# SCH_AirQuality.net
KiCad netlist of a schematic drawn in EasyEDA
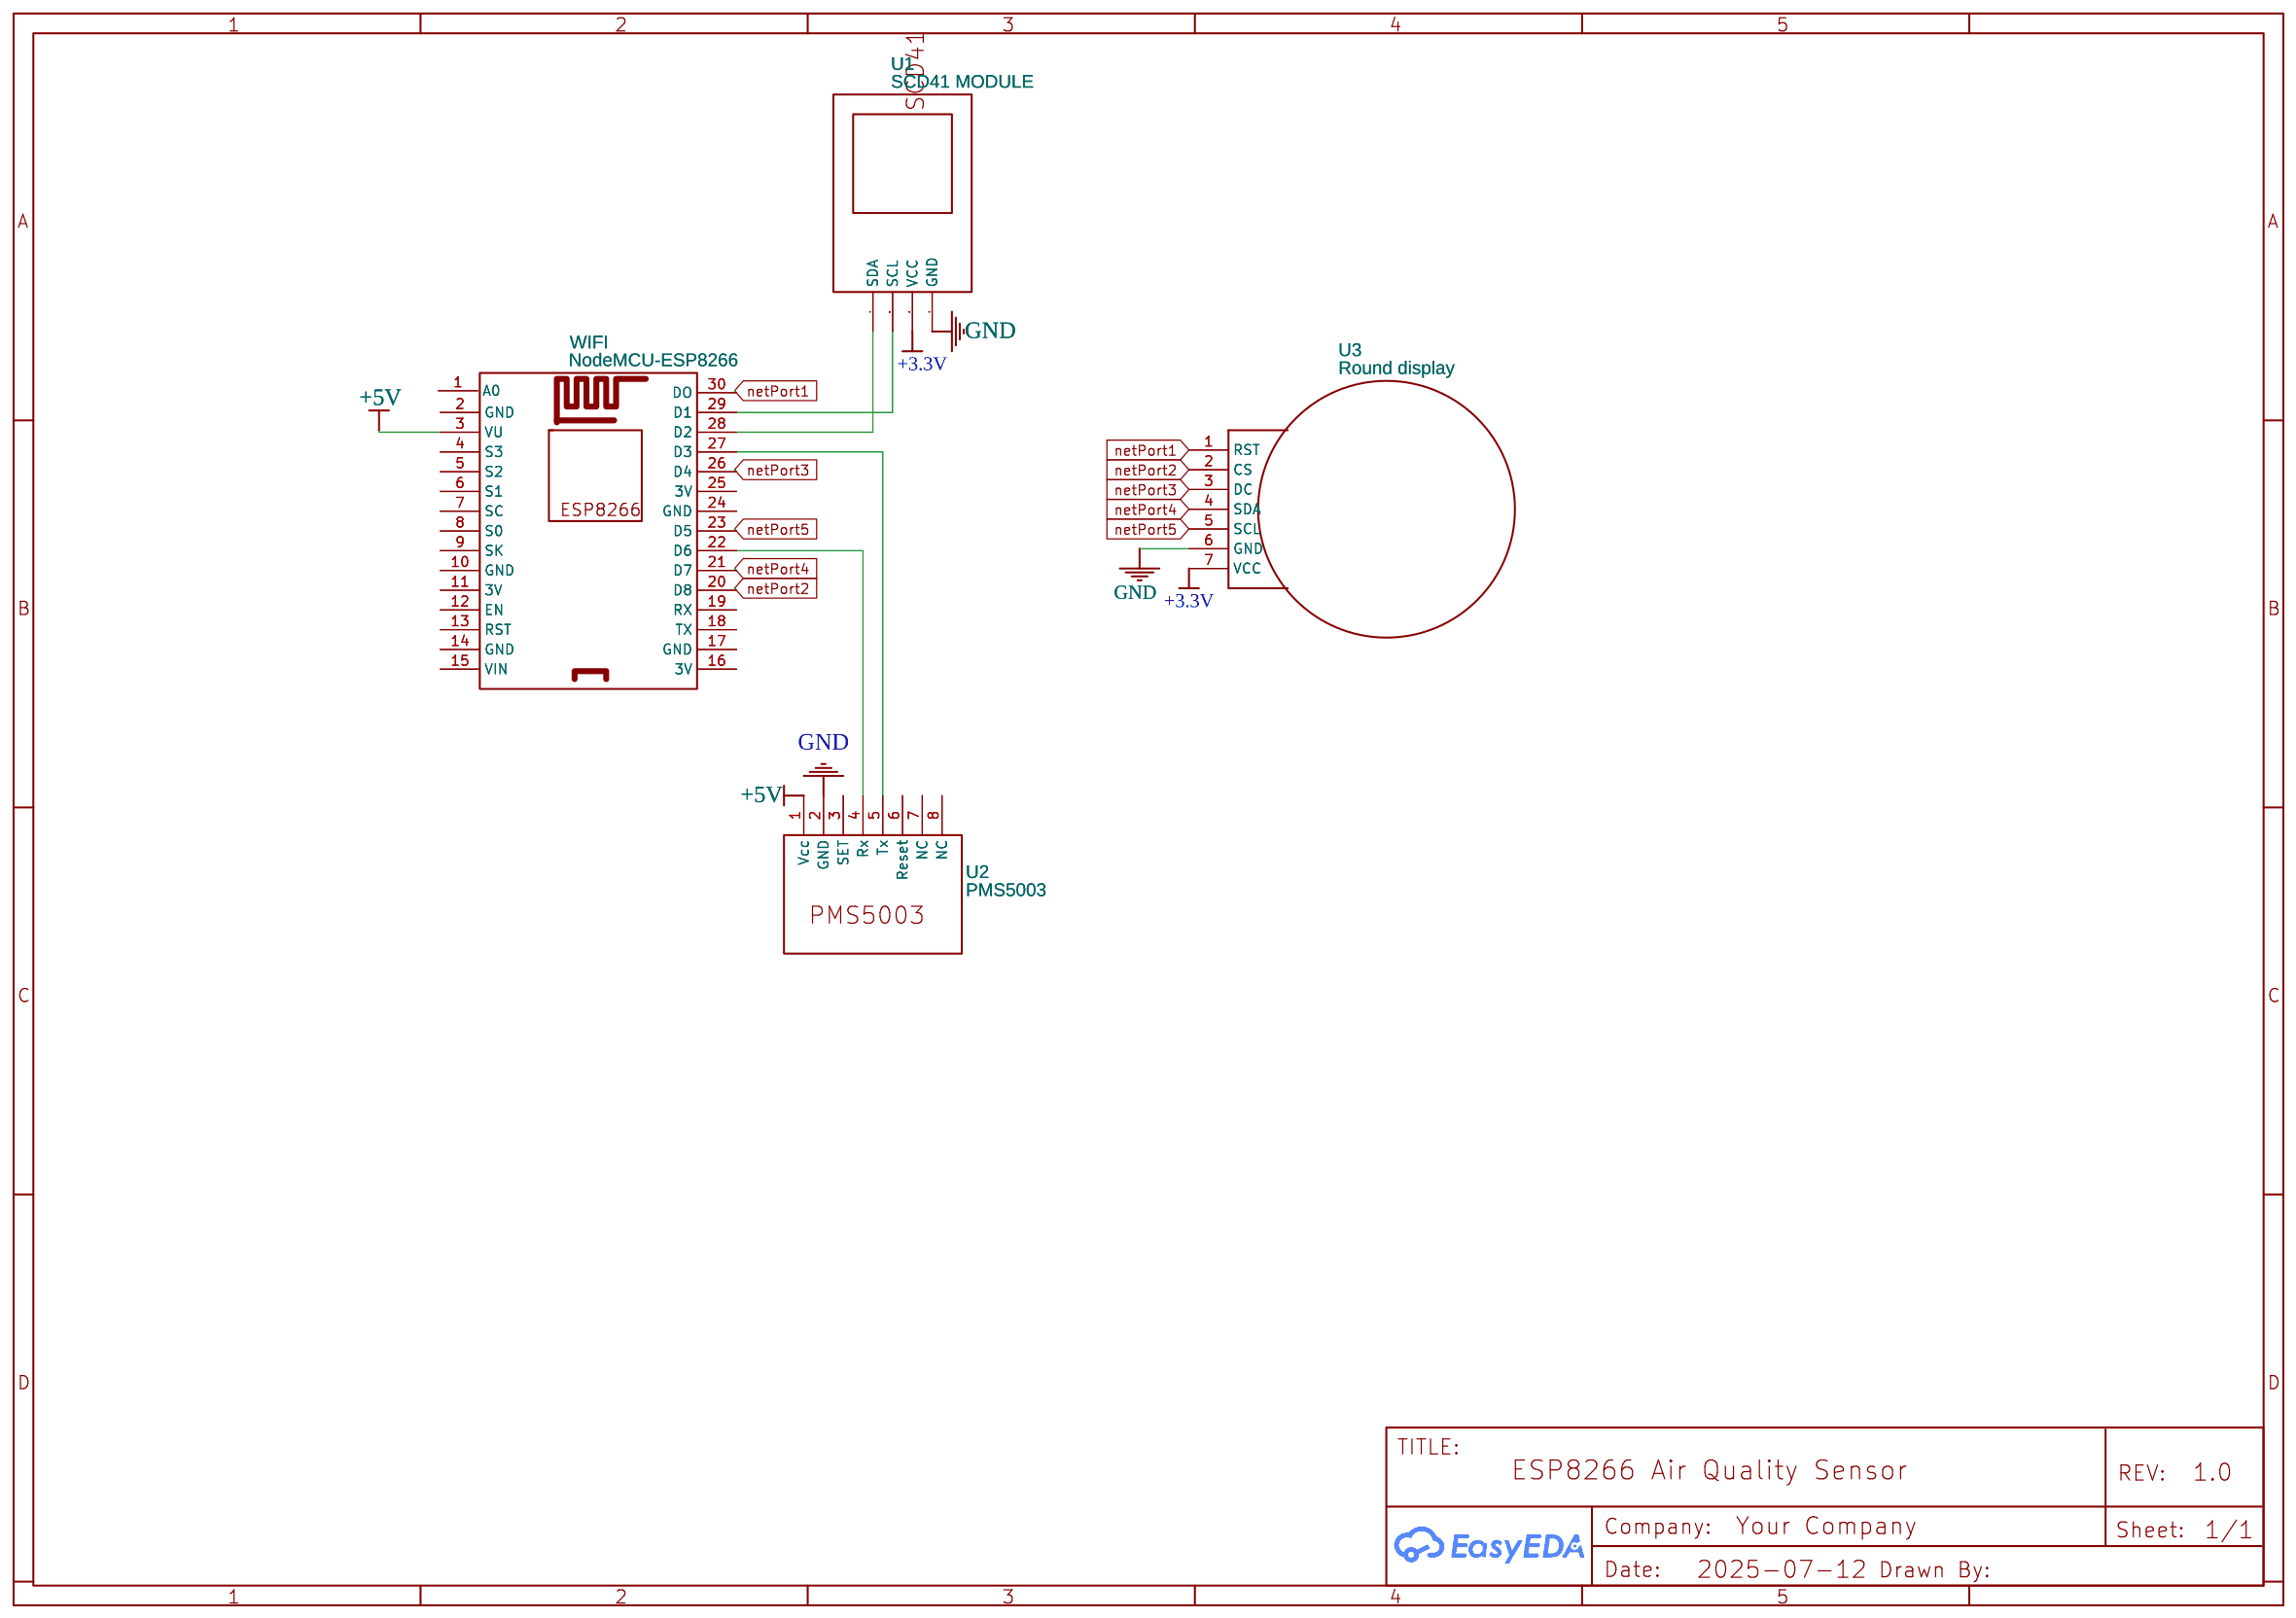
[diagram p0: schematic sheet]

(export (version "E")
  (design (tool "Eeschema 10.0.6"))
  (components
    (comp (ref "U1") (value "SCD41 MODULE") (libsource (lib "") (part "SCD41 MODULE")))
    (comp (ref "U2") (value "PMS5003") (libsource (lib "") (part "PMS5003")))
    (comp (ref "U3") (value "Round display") (libsource (lib "") (part "Round display")))
    (comp (ref "WIFI")
      (value "NodeMCU-ESP8266")
      (fields (field (name "Manufacturer Part") "NodeMCU-ESP8266 (S)"))
      (libsource (lib "") (part "NodeMCU-ESP8266"))
    )
  )
  (nets
    (net (code "1") (name "+3.3V") (class "Default")
      (node (ref "U1") (pin "2") (pinfunction "VCC_2") (pintype "unspecified"))
      (node (ref "U3") (pin "7") (pinfunction "VCC_7") (pintype "unspecified"))
    )
    (net (code "2") (name "+5V") (class "Default")
      (node (ref "U2") (pin "1") (pinfunction "Vcc_1") (pintype "unspecified"))
      (node (ref "WIFI") (pin "3") (pinfunction "VU_3") (pintype "unspecified"))
    )
    (net (code "3") (name "GND") (class "Default")
      (node (ref "U1") (pin "1") (pinfunction "GND_1") (pintype "unspecified"))
      (node (ref "U2") (pin "2") (pinfunction "GND_2") (pintype "unspecified"))
      (node (ref "U3") (pin "6") (pinfunction "GND_6") (pintype "unspecified"))
    )
    (net (code "4") (name "Net-(U1-SCL)") (class "Default")
      (node (ref "U1") (pin "3") (pinfunction "SCL_3") (pintype "unspecified"))
      (node (ref "WIFI") (pin "29") (pinfunction "D1_29") (pintype "unspecified"))
    )
    (net (code "5") (name "Net-(U1-SDA)") (class "Default")
      (node (ref "U1") (pin "4") (pinfunction "SDA_4") (pintype "unspecified"))
      (node (ref "WIFI") (pin "28") (pinfunction "D2_28") (pintype "unspecified"))
    )
    (net (code "6") (name "Net-(U2-Rx)") (class "Default")
      (node (ref "U2") (pin "4") (pinfunction "Rx_4") (pintype "unspecified"))
      (node (ref "WIFI") (pin "22") (pinfunction "D6_22") (pintype "unspecified"))
    )
    (net (code "7") (name "Net-(U2-Tx)") (class "Default")
      (node (ref "U2") (pin "5") (pinfunction "Tx_5") (pintype "unspecified"))
      (node (ref "WIFI") (pin "27") (pinfunction "D3_27") (pintype "unspecified"))
    )
    (net (code "8") (name "netPort1") (class "Default")
      (node (ref "U3") (pin "1") (pinfunction "RST_1") (pintype "unspecified"))
      (node (ref "WIFI") (pin "30") (pinfunction "DO_30") (pintype "unspecified"))
    )
    (net (code "9") (name "netPort2") (class "Default")
      (node (ref "U3") (pin "2") (pinfunction "CS_2") (pintype "unspecified"))
      (node (ref "WIFI") (pin "20") (pinfunction "D8_20") (pintype "unspecified"))
    )
    (net (code "10") (name "netPort3") (class "Default")
      (node (ref "U3") (pin "3") (pinfunction "DC_3") (pintype "unspecified"))
      (node (ref "WIFI") (pin "26") (pinfunction "D4_26") (pintype "unspecified"))
    )
    (net (code "11") (name "netPort4") (class "Default")
      (node (ref "U3") (pin "4") (pinfunction "SDA_4") (pintype "unspecified"))
      (node (ref "WIFI") (pin "21") (pinfunction "D7_21") (pintype "unspecified"))
    )
    (net (code "12") (name "netPort5") (class "Default")
      (node (ref "U3") (pin "5") (pinfunction "SCL_5") (pintype "unspecified"))
      (node (ref "WIFI") (pin "23") (pinfunction "D5_23") (pintype "unspecified"))
    )
    (net (code "13") (name "unconnected-(U2-NC-Pad7)") (class "Default")
      (node (ref "U2") (pin "7") (pinfunction "NC_7") (pintype "unspecified"))
    )
    (net (code "14") (name "unconnected-(U2-NC-Pad8)") (class "Default")
      (node (ref "U2") (pin "8") (pinfunction "NC_8") (pintype "unspecified"))
    )
    (net (code "15") (name "unconnected-(U2-Reset-Pad6)") (class "Default")
      (node (ref "U2") (pin "6") (pinfunction "Reset_6") (pintype "unspecified"))
    )
    (net (code "16") (name "unconnected-(U2-SET-Pad3)") (class "Default")
      (node (ref "U2") (pin "3") (pinfunction "SET_3") (pintype "unspecified"))
    )
    (net (code "17") (name "unconnected-(WIFI-3V-Pad11)") (class "Default")
      (node (ref "WIFI") (pin "11") (pinfunction "3V_11") (pintype "unspecified"))
    )
    (net (code "18") (name "unconnected-(WIFI-3V-Pad16)") (class "Default")
      (node (ref "WIFI") (pin "16") (pinfunction "3V_16") (pintype "unspecified"))
    )
    (net (code "19") (name "unconnected-(WIFI-3V-Pad25)") (class "Default")
      (node (ref "WIFI") (pin "25") (pinfunction "3V_25") (pintype "unspecified"))
    )
    (net (code "20") (name "unconnected-(WIFI-A0-Pad1)") (class "Default")
      (node (ref "WIFI") (pin "1") (pinfunction "A0_1") (pintype "unspecified"))
    )
    (net (code "21") (name "unconnected-(WIFI-EN-Pad12)") (class "Default")
      (node (ref "WIFI") (pin "12") (pinfunction "EN_12") (pintype "unspecified"))
    )
    (net (code "22") (name "unconnected-(WIFI-GND-Pad2)") (class "Default")
      (node (ref "WIFI") (pin "2") (pinfunction "GND_2") (pintype "unspecified"))
    )
    (net (code "23") (name "unconnected-(WIFI-GND-Pad10)") (class "Default")
      (node (ref "WIFI") (pin "10") (pinfunction "GND_10") (pintype "unspecified"))
    )
    (net (code "24") (name "unconnected-(WIFI-GND-Pad14)") (class "Default")
      (node (ref "WIFI") (pin "14") (pinfunction "GND_14") (pintype "unspecified"))
    )
    (net (code "25") (name "unconnected-(WIFI-GND-Pad17)") (class "Default")
      (node (ref "WIFI") (pin "17") (pinfunction "GND_17") (pintype "unspecified"))
    )
    (net (code "26") (name "unconnected-(WIFI-GND-Pad24)") (class "Default")
      (node (ref "WIFI") (pin "24") (pinfunction "GND_24") (pintype "unspecified"))
    )
    (net (code "27") (name "unconnected-(WIFI-RST-Pad13)") (class "Default")
      (node (ref "WIFI") (pin "13") (pinfunction "RST_13") (pintype "unspecified"))
    )
    (net (code "28") (name "unconnected-(WIFI-RX-Pad19)") (class "Default")
      (node (ref "WIFI") (pin "19") (pinfunction "RX_19") (pintype "unspecified"))
    )
    (net (code "29") (name "unconnected-(WIFI-S0-Pad8)") (class "Default")
      (node (ref "WIFI") (pin "8") (pinfunction "S0_8") (pintype "unspecified"))
    )
    (net (code "30") (name "unconnected-(WIFI-S1-Pad6)") (class "Default")
      (node (ref "WIFI") (pin "6") (pinfunction "S1_6") (pintype "unspecified"))
    )
    (net (code "31") (name "unconnected-(WIFI-S2-Pad5)") (class "Default")
      (node (ref "WIFI") (pin "5") (pinfunction "S2_5") (pintype "unspecified"))
    )
    (net (code "32") (name "unconnected-(WIFI-S3-Pad4)") (class "Default")
      (node (ref "WIFI") (pin "4") (pinfunction "S3_4") (pintype "unspecified"))
    )
    (net (code "33") (name "unconnected-(WIFI-SC-Pad7)") (class "Default")
      (node (ref "WIFI") (pin "7") (pinfunction "SC_7") (pintype "unspecified"))
    )
    (net (code "34") (name "unconnected-(WIFI-SK-Pad9)") (class "Default")
      (node (ref "WIFI") (pin "9") (pinfunction "SK_9") (pintype "unspecified"))
    )
    (net (code "35") (name "unconnected-(WIFI-TX-Pad18)") (class "Default")
      (node (ref "WIFI") (pin "18") (pinfunction "TX_18") (pintype "unspecified"))
    )
    (net (code "36") (name "unconnected-(WIFI-VIN-Pad15)") (class "Default")
      (node (ref "WIFI") (pin "15") (pinfunction "VIN_15") (pintype "unspecified"))
    )
  )
)
